# Sheet6.net
KiCad netlist of a schematic drawn in Altium Designer
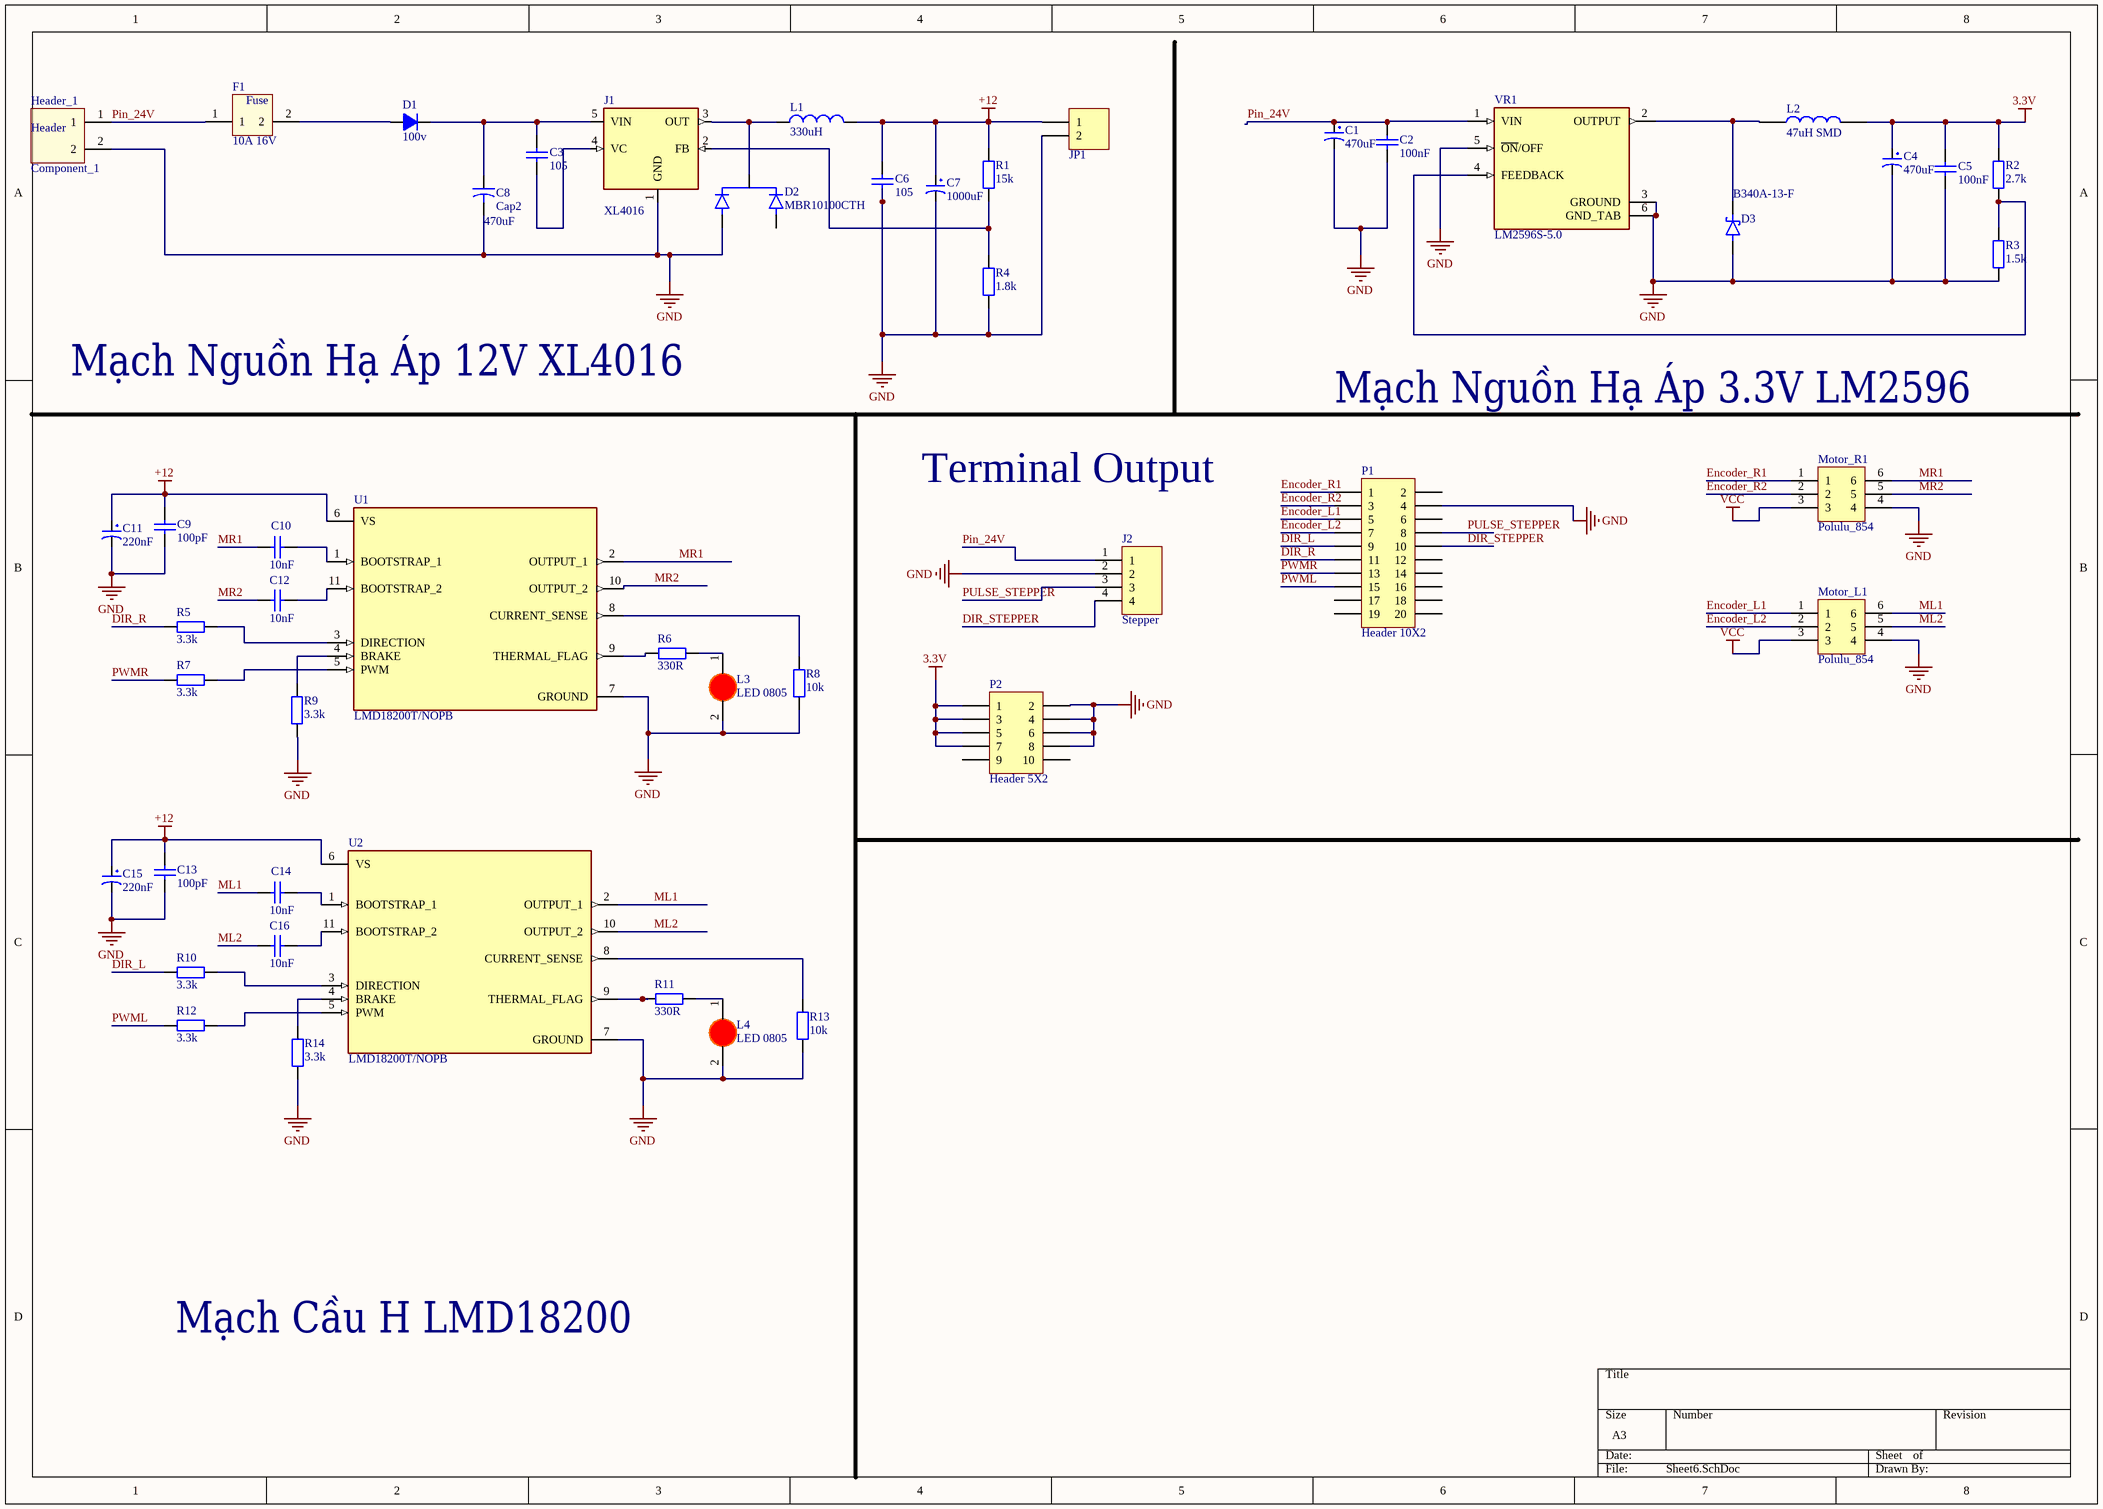
[diagram p0: Sheet6.SchDoc]

(export (version "E")
  (design (tool "Eeschema 10.0.6"))
  (components
    (comp (ref "C1")
      (value "470uF")
      (footprint "tu hoa 8mm")
      (description "Cắm")
      (libsource (lib "Altium_Lib_by_KhueNguyenCreator") (part "Tu Hoa 470uF 16V 8x11"))
    )
    (comp (ref "C2")
      (value "100nF")
      (footprint "tu tantalum dip5.08")
      (description "Cắm")
      (libsource (lib "Altium_Lib_by_KhueNguyenCreator") (part "Tu tantalum 100nF 50V 20% DIP5.08"))
    )
    (comp (ref "C3")
      (value "105")
      (footprint "tu 0805")
      (description "Dán")
      (libsource (lib "Altium_Lib_by_KhueNguyenCreator") (part "Tu 0805 105 50V 10%"))
    )
    (comp (ref "C4")
      (value "470uF")
      (footprint "tu hoa 8mm")
      (description "Cắm")
      (libsource (lib "Altium_Lib_by_KhueNguyenCreator") (part "Tu Hoa 470uF 16V 8x11"))
    )
    (comp (ref "C5")
      (value "100nF")
      (footprint "tu tantalum dip5.08")
      (description "Cắm")
      (libsource (lib "Altium_Lib_by_KhueNguyenCreator") (part "Tu tantalum 100nF 50V 20% DIP5.08"))
    )
    (comp (ref "C6")
      (value "105")
      (footprint "tu 0805")
      (description "Dán")
      (libsource (lib "Altium_Lib_by_KhueNguyenCreator") (part "Tu 0805 105 50V 10%"))
    )
    (comp (ref "C7")
      (value "1000uF")
      (footprint "tu hoa 13mm")
      (description "Cắm")
      (libsource (lib "Altium_Lib_by_KhueNguyenCreator") (part "Tu Hoa 1000uF 50V 13x26"))
    )
    (comp (ref "C8")
      (value "Cap2")
      (footprint "CAPR5-4X5")
      (description "Capacitor")
      (fields (field (name "ALTIUM_VALUE") "470uF") (field (name "PUBLISHER") "Altium Limited"))
      (libsource (lib "Miscellaneous Devices") (part "Cap2"))
    )
    (comp (ref "C9")
      (value "100pF")
      (footprint "tu 1206")
      (description "Dán")
      (libsource (lib "Altium_Lib_by_KhueNguyenCreator") (part "Tu 1206 100pF 50V 5%"))
    )
    (comp (ref "C10")
      (value "10nF")
      (footprint "tu tantalum dip5.08")
      (description "Cắm")
      (libsource (lib "Altium_Lib_by_KhueNguyenCreator") (part "Tu tantalum 10nF DIP5.08"))
    )
    (comp (ref "C11")
      (value "220nF")
      (footprint "tu hoa 8mm")
      (description "Cắm")
      (libsource (lib "Altium_Lib_by_KhueNguyenCreator") (part "Tu Hoa 220uF 35V 8x12"))
    )
    (comp (ref "C12")
      (value "10nF")
      (footprint "tu tantalum dip5.08")
      (description "Cắm")
      (libsource (lib "Altium_Lib_by_KhueNguyenCreator") (part "Tu tantalum 10nF DIP5.08"))
    )
    (comp (ref "C13")
      (value "100pF")
      (footprint "tu 1206")
      (description "Dán")
      (libsource (lib "Altium_Lib_by_KhueNguyenCreator") (part "Tu 1206 100pF 50V 5%"))
    )
    (comp (ref "C14")
      (value "10nF")
      (footprint "tu tantalum dip5.08")
      (description "Cắm")
      (libsource (lib "Altium_Lib_by_KhueNguyenCreator") (part "Tu tantalum 10nF DIP5.08"))
    )
    (comp (ref "C15")
      (value "220nF")
      (footprint "tu hoa 8mm")
      (description "Cắm")
      (libsource (lib "Altium_Lib_by_KhueNguyenCreator") (part "Tu Hoa 220uF 35V 8x12"))
    )
    (comp (ref "C16")
      (value "10nF")
      (footprint "tu tantalum dip5.08")
      (description "Cắm")
      (libsource (lib "Altium_Lib_by_KhueNguyenCreator") (part "Tu tantalum 10nF DIP5.08"))
    )
    (comp (ref "D1")
      (value "100v")
      (footprint "DIODE 1A")
      (description "Cắm")
      (libsource (lib "Altium_Lib_by_KhueNguyenCreator") (part "Diode 1N4007"))
    )
    (comp (ref "D2")
      (value "MBR10100CTH")
      (footprint "TO254P1050X476X2020-3")
      (description "10A, 100V, Schottky Rectifier")
      (fields (field (name "MF") "Taiwan Semiconductor"))
      (libsource (lib "MBR10100CTH") (part "MBR10100CTH"))
    )
    (comp (ref "D3")
      (value "B340A-13-F")
      (footprint "DIOM5226X240N")
      (description "Diode Schottky 40V 3A Surface Mount SMA")
      (fields (field (name "MF") "Diodes Inc."))
      (libsource (lib "Altium_Lib_by_KhueNguyenCreator") (part "B340A-13-F"))
    )
    (comp (ref "F1")
      (value "10A 16V")
      (footprint "Auto_Fuse")
      (libsource (lib "Thu_vien_KA_01") (part "Auto_Fuse_10A"))
    )
    (comp (ref "Header_1")
      (value "Component_1")
      (footprint "CONN-TH_2P-P9.50_HB9500-9.5-2P")
      (libsource (lib "Header_2Pin") (part "Component_1"))
    )
    (comp (ref "J1")
      (value "XL4016")
      (footprint "LM2576T2")
      (fields (field (name "MF") "XLSEMI"))
      (libsource (lib "XL4016") (part "XL4016"))
    )
    (comp (ref "J2")
      (value "Stepper")
      (footprint "CON4_78_B4B-PH-K-S(LF)(SN)")
      (description "Connector Header Through Hole 4 position 0.079\" (2.00mm)")
      (fields
        (field (name "MANUFACTURER PART NUMBER") "B4B-PH-K-S(LF)(SN)")
        (field (name "MANUFACTURER") "JST")
      )
      (libsource (lib "Altium_Lib_by_KhueNguyenCreator") (part "CON-PLG_4X1-78-ST-TH"))
    )
    (comp (ref "JP1")
      (value "Header 2_1")
      (footprint "HED2")
      (description "Header, 2-Pin")
      (fields (field (name "MANUFACTURER") "Generic Components"))
      (libsource (lib "syhaunguyen") (part "Header 2_1"))
    )
    (comp (ref "L1")
      (value "330uH")
      (footprint "IND_30.1MM_TH")
      (description "330uH-10A-CHINESE INDUCTOR")
      (fields (field (name "MANUFACTURER PART NUMBER") "NA"))
      (libsource (lib "Altium_Lib_by_KhueNguyenCreator") (part "IND_330uH-10A-TH"))
    )
    (comp (ref "L2")
      (value "47uH SMD")
      (footprint "Cuon Cam 7x7x5")
      (description "Dán")
      (libsource (lib "Altium_Lib_by_KhueNguyenCreator") (part "CUON CAM 47uH SMD"))
    )
    (comp (ref "L3")
      (value "LED 0805")
      (footprint "LED-0805-Red")
      (description "Dán")
      (libsource (lib "Altium_Lib_by_KhueNguyenCreator") (part "LED 0805 Do"))
    )
    (comp (ref "L4")
      (value "LED 0805")
      (footprint "LED-0805-Red")
      (description "Dán")
      (libsource (lib "Altium_Lib_by_KhueNguyenCreator") (part "LED 0805 Do"))
    )
    (comp (ref "Motor_L1")
      (value "Polulu_854")
      (footprint "CON6_100_59D78_TH_ST - duplicate")
      (fields (field (name "MANUFACTURER") "NA"))
      (libsource (lib "Altium_Lib_by_KhueNguyenCreator") (part "CON-PLG_2X3-100-ST-TH"))
    )
    (comp (ref "Motor_R1")
      (value "Polulu_854")
      (footprint "CON6_100_59D78_TH_ST - duplicate")
      (fields (field (name "MANUFACTURER") "NA"))
      (libsource (lib "Altium_Lib_by_KhueNguyenCreator") (part "CON-PLG_2X3-100-ST-TH"))
    )
    (comp (ref "P1")
      (value "Header 10X2")
      (footprint "HDR2X10")
      (description "Header, 10-Pin, Dual row")
      (fields (field (name "PUBLISHER") "Altium Limited"))
      (libsource (lib "Miscellaneous Connectors") (part "Header 10X2"))
    )
    (comp (ref "P2")
      (value "Header 5X2")
      (footprint "HDR2X5")
      (description "Header, 5-Pin, Dual row")
      (fields (field (name "PUBLISHER") "Altium Limited"))
      (libsource (lib "My library altium") (part "Header 5X2"))
    )
    (comp (ref "R1")
      (value "15k")
      (footprint "tro vach 1/4w")
      (description "Cắm")
      (libsource (lib "Altium_Lib_by_KhueNguyenCreator") (part "Tro Vach 1/4W 5% 15k"))
    )
    (comp (ref "R2")
      (value "2.7k")
      (footprint "tro smd 0805")
      (description "Dán")
      (libsource (lib "Altium_Lib_by_KhueNguyenCreator") (part "Tro 0805 5% 2.7k"))
    )
    (comp (ref "R3")
      (value "1.5k")
      (footprint "tro smd 0805")
      (description "Dán")
      (libsource (lib "Altium_Lib_by_KhueNguyenCreator") (part "Tro 0805 5% 1.5k"))
    )
    (comp (ref "R4")
      (value "1.8k")
      (footprint "tro vach 1/4w")
      (description "Cắm")
      (libsource (lib "Altium_Lib_by_KhueNguyenCreator") (part "Tro Vach 1/4W 5% 1.8k"))
    )
    (comp (ref "R5")
      (value "3.3k")
      (footprint "tro smd 0805")
      (description "Dán")
      (libsource (lib "Altium_Lib_by_KhueNguyenCreator") (part "Tro 0805 5% 3.3k"))
    )
    (comp (ref "R6")
      (value "330R")
      (footprint "Tro SMD 0805")
      (description "Dán")
      (libsource (lib "Altium_Lib_by_KhueNguyenCreator") (part "Tro 0805 5% 330R"))
    )
    (comp (ref "R7")
      (value "3.3k")
      (footprint "tro smd 0805")
      (description "Dán")
      (libsource (lib "Altium_Lib_by_KhueNguyenCreator") (part "Tro 0805 5% 3.3k"))
    )
    (comp (ref "R8")
      (value "10k")
      (footprint "tro smd 0805")
      (description "Dán")
      (libsource (lib "Altium_Lib_by_KhueNguyenCreator") (part "Tro 0805 5% 10k"))
    )
    (comp (ref "R9")
      (value "3.3k")
      (footprint "tro smd 0805")
      (description "Dán")
      (libsource (lib "Altium_Lib_by_KhueNguyenCreator") (part "Tro 0805 5% 3.3k"))
    )
    (comp (ref "R10")
      (value "3.3k")
      (footprint "tro smd 0805")
      (description "Dán")
      (libsource (lib "Altium_Lib_by_KhueNguyenCreator") (part "Tro 0805 5% 3.3k"))
    )
    (comp (ref "R11")
      (value "330R")
      (footprint "Tro SMD 0805")
      (description "Dán")
      (libsource (lib "Altium_Lib_by_KhueNguyenCreator") (part "Tro 0805 5% 330R"))
    )
    (comp (ref "R12")
      (value "3.3k")
      (footprint "tro smd 0805")
      (description "Dán")
      (libsource (lib "Altium_Lib_by_KhueNguyenCreator") (part "Tro 0805 5% 3.3k"))
    )
    (comp (ref "R13")
      (value "10k")
      (footprint "tro smd 0805")
      (description "Dán")
      (libsource (lib "Altium_Lib_by_KhueNguyenCreator") (part "Tro 0805 5% 10k"))
    )
    (comp (ref "R14")
      (value "3.3k")
      (footprint "tro smd 0805")
      (description "Dán")
      (libsource (lib "Altium_Lib_by_KhueNguyenCreator") (part "Tro 0805 5% 3.3k"))
    )
    (comp (ref "U1")
      (value "LMD18200T/NOPB")
      (footprint "LMD18200")
      (libsource (lib "Thu_vien_KA_01") (part "LMD18200T/NOPB"))
    )
    (comp (ref "U2")
      (value "LMD18200T/NOPB")
      (footprint "LMD18200")
      (libsource (lib "Thu_vien_KA_01") (part "LMD18200T/NOPB"))
    )
    (comp (ref "VR1")
      (value "LM2596S-5.0")
      (footprint "TO170P1524X483-6N")
      (description "SIMPLE SWITCHER&reg; 4.5V to 40V, 3A Low Component Count Step-Down Regulator")
      (fields (field (name "MP") "LM2596S-5.0/NOPB") (field (name "MF") "Texas Instruments"))
      (libsource (lib "LM2596S-5.0") (part "LM2596S-5.0"))
    )
  )
  (nets
    (net (code "1") (name "+12") (class "Default")
      (node (ref "C11") (pin "1") (pinfunction "1_1") (pintype "passive"))
      (node (ref "C13") (pin "1") (pinfunction "1_1") (pintype "passive"))
      (node (ref "C15") (pin "1") (pinfunction "1_1") (pintype "passive"))
      (node (ref "C6") (pin "1") (pinfunction "1_1") (pintype "passive"))
      (node (ref "C7") (pin "1") (pinfunction "1_1") (pintype "passive"))
      (node (ref "C9") (pin "1") (pinfunction "1_1") (pintype "passive"))
      (node (ref "JP1") (pin "1") (pinfunction "1_1") (pintype "passive"))
      (node (ref "L1") (pin "2") (pinfunction "2_2") (pintype "passive"))
      (node (ref "R1") (pin "2") (pinfunction "2_2") (pintype "passive"))
      (node (ref "U1") (pin "6") (pinfunction "VS_6") (pintype "power_in"))
      (node (ref "U2") (pin "6") (pinfunction "VS_6") (pintype "power_in"))
    )
    (net (code "2") (name "/DIR_L") (class "Default")
      (node (ref "P1") (pin "9") (pinfunction "9_9") (pintype "passive"))
      (node (ref "R10") (pin "1") (pinfunction "1_1") (pintype "passive"))
    )
    (net (code "3") (name "/DIR_R") (class "Default")
      (node (ref "P1") (pin "11") (pinfunction "11_11") (pintype "passive"))
      (node (ref "R5") (pin "1") (pinfunction "1_1") (pintype "passive"))
    )
    (net (code "4") (name "/DIR_STEPPER") (class "Default")
      (node (ref "J2") (pin "4") (pinfunction "4_4") (pintype "passive"))
      (node (ref "P1") (pin "10") (pinfunction "10_10") (pintype "passive"))
    )
    (net (code "5") (name "/Encoder_L1") (class "Default")
      (node (ref "Motor_L1") (pin "1") (pinfunction "1_1") (pintype "passive"))
      (node (ref "P1") (pin "5") (pinfunction "5_5") (pintype "passive"))
    )
    (net (code "6") (name "/Encoder_L2") (class "Default")
      (node (ref "Motor_L1") (pin "2") (pinfunction "2_2") (pintype "passive"))
      (node (ref "P1") (pin "7") (pinfunction "7_7") (pintype "passive"))
    )
    (net (code "7") (name "/Encoder_R1") (class "Default")
      (node (ref "Motor_R1") (pin "1") (pinfunction "1_1") (pintype "passive"))
      (node (ref "P1") (pin "1") (pinfunction "1_1") (pintype "passive"))
    )
    (net (code "8") (name "/Encoder_R2") (class "Default")
      (node (ref "Motor_R1") (pin "2") (pinfunction "2_2") (pintype "passive"))
      (node (ref "P1") (pin "3") (pinfunction "3_3") (pintype "passive"))
    )
    (net (code "9") (name "/ML1") (class "Default")
      (node (ref "C14") (pin "2") (pinfunction "2_2") (pintype "passive"))
      (node (ref "Motor_L1") (pin "6") (pinfunction "6_6") (pintype "passive"))
      (node (ref "U2") (pin "2") (pinfunction "OUTPUT_1_2") (pintype "output"))
    )
    (net (code "10") (name "/ML2") (class "Default")
      (node (ref "C16") (pin "2") (pinfunction "2_2") (pintype "passive"))
      (node (ref "Motor_L1") (pin "5") (pinfunction "5_5") (pintype "passive"))
      (node (ref "U2") (pin "10") (pinfunction "OUTPUT_2_10") (pintype "output"))
    )
    (net (code "11") (name "/MR1") (class "Default")
      (node (ref "C10") (pin "2") (pinfunction "2_2") (pintype "passive"))
      (node (ref "Motor_R1") (pin "6") (pinfunction "6_6") (pintype "passive"))
      (node (ref "U1") (pin "2") (pinfunction "OUTPUT_1_2") (pintype "output"))
    )
    (net (code "12") (name "/MR2") (class "Default")
      (node (ref "C12") (pin "2") (pinfunction "2_2") (pintype "passive"))
      (node (ref "Motor_R1") (pin "5") (pinfunction "5_5") (pintype "passive"))
      (node (ref "U1") (pin "10") (pinfunction "OUTPUT_2_10") (pintype "output"))
    )
    (net (code "13") (name "/PULSE_STEPPER") (class "Default")
      (node (ref "J2") (pin "3") (pinfunction "3_3") (pintype "passive"))
      (node (ref "P1") (pin "8") (pinfunction "8_8") (pintype "passive"))
    )
    (net (code "14") (name "/PWML") (class "Default")
      (node (ref "P1") (pin "15") (pinfunction "15_15") (pintype "passive"))
      (node (ref "R12") (pin "1") (pinfunction "1_1") (pintype "passive"))
    )
    (net (code "15") (name "/PWMR") (class "Default")
      (node (ref "P1") (pin "13") (pinfunction "13_13") (pintype "passive"))
      (node (ref "R7") (pin "1") (pinfunction "1_1") (pintype "passive"))
    )
    (net (code "16") (name "/Pin_24V") (class "Default")
      (node (ref "C1") (pin "1") (pinfunction "1_1") (pintype "passive"))
      (node (ref "C2") (pin "1") (pinfunction "1_1") (pintype "passive"))
      (node (ref "F1") (pin "1") (pinfunction "1_1") (pintype "passive"))
      (node (ref "Header_1") (pin "1") (pinfunction "1_1") (pintype "passive"))
      (node (ref "J2") (pin "1") (pinfunction "1_1") (pintype "passive"))
      (node (ref "VR1") (pin "1") (pinfunction "VIN_1") (pintype "input"))
    )
    (net (code "17") (name "3.3V") (class "Default")
      (node (ref "C4") (pin "1") (pinfunction "1_1") (pintype "passive"))
      (node (ref "C5") (pin "1") (pinfunction "1_1") (pintype "passive"))
      (node (ref "L2") (pin "2") (pinfunction "2_2") (pintype "passive"))
      (node (ref "P2") (pin "1") (pinfunction "1_1") (pintype "passive"))
      (node (ref "P2") (pin "3") (pinfunction "3_3") (pintype "passive"))
      (node (ref "P2") (pin "5") (pinfunction "5_5") (pintype "passive"))
      (node (ref "P2") (pin "7") (pinfunction "7_7") (pintype "passive"))
      (node (ref "R2") (pin "2") (pinfunction "2_2") (pintype "passive"))
    )
    (net (code "18") (name "GND") (class "Default")
      (node (ref "C1") (pin "2") (pinfunction "2_2") (pintype "passive"))
      (node (ref "C11") (pin "2") (pinfunction "2_2") (pintype "passive"))
      (node (ref "C13") (pin "2") (pinfunction "2_2") (pintype "passive"))
      (node (ref "C15") (pin "2") (pinfunction "2_2") (pintype "passive"))
      (node (ref "C2") (pin "2") (pinfunction "2_2") (pintype "passive"))
      (node (ref "C4") (pin "2") (pinfunction "2_2") (pintype "passive"))
      (node (ref "C5") (pin "2") (pinfunction "2_2") (pintype "passive"))
      (node (ref "C6") (pin "2") (pinfunction "2_2") (pintype "passive"))
      (node (ref "C7") (pin "2") (pinfunction "2_2") (pintype "passive"))
      (node (ref "C8") (pin "2") (pinfunction "2_2") (pintype "passive"))
      (node (ref "C9") (pin "2") (pinfunction "2_2") (pintype "passive"))
      (node (ref "D2") (pin "1") (pinfunction "A1_1") (pintype "passive"))
      (node (ref "D3") (pin "A") (pinfunction "A_A") (pintype "passive"))
      (node (ref "Header_1") (pin "2") (pinfunction "2_2") (pintype "passive"))
      (node (ref "J1") (pin "1") (pinfunction "GND_1") (pintype "power_in"))
      (node (ref "J2") (pin "2") (pinfunction "2_2") (pintype "passive"))
      (node (ref "JP1") (pin "2") (pinfunction "2_2") (pintype "passive"))
      (node (ref "L3") (pin "2") (pinfunction "K_2") (pintype "passive"))
      (node (ref "L4") (pin "2") (pinfunction "K_2") (pintype "passive"))
      (node (ref "Motor_L1") (pin "4") (pinfunction "4_4") (pintype "passive"))
      (node (ref "Motor_R1") (pin "4") (pinfunction "4_4") (pintype "passive"))
      (node (ref "P1") (pin "4") (pinfunction "4_4") (pintype "passive"))
      (node (ref "P2") (pin "2") (pinfunction "2_2") (pintype "passive"))
      (node (ref "P2") (pin "4") (pinfunction "4_4") (pintype "passive"))
      (node (ref "P2") (pin "6") (pinfunction "6_6") (pintype "passive"))
      (node (ref "P2") (pin "8") (pinfunction "8_8") (pintype "passive"))
      (node (ref "R13") (pin "1") (pinfunction "1_1") (pintype "passive"))
      (node (ref "R14") (pin "1") (pinfunction "1_1") (pintype "passive"))
      (node (ref "R3") (pin "1") (pinfunction "1_1") (pintype "passive"))
      (node (ref "R4") (pin "1") (pinfunction "1_1") (pintype "passive"))
      (node (ref "R8") (pin "1") (pinfunction "1_1") (pintype "passive"))
      (node (ref "R9") (pin "1") (pinfunction "1_1") (pintype "passive"))
      (node (ref "U1") (pin "7") (pinfunction "GROUND_7") (pintype "power_in"))
      (node (ref "U2") (pin "7") (pinfunction "GROUND_7") (pintype "power_in"))
      (node (ref "VR1") (pin "3") (pinfunction "GROUND_3") (pintype "power_in"))
      (node (ref "VR1") (pin "5") (pinfunction "~{ON}/OFF_5") (pintype "input"))
      (node (ref "VR1") (pin "6") (pinfunction "GND_TAB_6") (pintype "power_in"))
    )
    (net (code "19") (name "Net-(D1-A)") (class "Default")
      (node (ref "D1") (pin "1") (pinfunction "A_1") (pintype "passive"))
      (node (ref "F1") (pin "2") (pinfunction "2_2") (pintype "passive"))
    )
    (net (code "20") (name "Net-(D1-K)") (class "Default")
      (node (ref "C3") (pin "1") (pinfunction "1_1") (pintype "passive"))
      (node (ref "C8") (pin "1") (pinfunction "1_1") (pintype "passive"))
      (node (ref "D1") (pin "2") (pinfunction "K_2") (pintype "passive"))
      (node (ref "J1") (pin "5") (pinfunction "VIN_5") (pintype "power_in"))
    )
    (net (code "21") (name "Net-(D2-C)") (class "Default")
      (node (ref "D2") (pin "2") (pinfunction "C_2") (pintype "passive"))
      (node (ref "J1") (pin "3") (pinfunction "OUT_3") (pintype "output"))
      (node (ref "L1") (pin "1") (pinfunction "1_1") (pintype "passive"))
    )
    (net (code "22") (name "Net-(J1-FB)") (class "Default")
      (node (ref "J1") (pin "2") (pinfunction "FB_2") (pintype "input"))
      (node (ref "R1") (pin "1") (pinfunction "1_1") (pintype "passive"))
      (node (ref "R4") (pin "2") (pinfunction "2_2") (pintype "passive"))
    )
    (net (code "23") (name "Net-(J1-VC)") (class "Default")
      (node (ref "C3") (pin "2") (pinfunction "2_2") (pintype "passive"))
      (node (ref "J1") (pin "4") (pinfunction "VC_4") (pintype "input"))
    )
    (net (code "24") (name "Net-(L3-A)") (class "Default")
      (node (ref "L3") (pin "1") (pinfunction "A_1") (pintype "passive"))
      (node (ref "R6") (pin "2") (pinfunction "2_2") (pintype "passive"))
    )
    (net (code "25") (name "Net-(L4-A)") (class "Default")
      (node (ref "L4") (pin "1") (pinfunction "A_1") (pintype "passive"))
      (node (ref "R11") (pin "2") (pinfunction "2_2") (pintype "passive"))
    )
    (net (code "26") (name "Net-(U1-BOOTSTRAP_1)") (class "Default")
      (node (ref "C10") (pin "1") (pinfunction "1_1") (pintype "passive"))
      (node (ref "U1") (pin "1") (pinfunction "BOOTSTRAP_1_1") (pintype "input"))
    )
    (net (code "27") (name "Net-(U1-BOOTSTRAP_2)") (class "Default")
      (node (ref "C12") (pin "1") (pinfunction "1_1") (pintype "passive"))
      (node (ref "U1") (pin "11") (pinfunction "BOOTSTRAP_2_11") (pintype "input"))
    )
    (net (code "28") (name "Net-(U1-BRAKE)") (class "Default")
      (node (ref "R9") (pin "2") (pinfunction "2_2") (pintype "passive"))
      (node (ref "U1") (pin "4") (pinfunction "BRAKE_4") (pintype "input"))
    )
    (net (code "29") (name "Net-(U1-CURRENT_SENSE)") (class "Default")
      (node (ref "R8") (pin "2") (pinfunction "2_2") (pintype "passive"))
      (node (ref "U1") (pin "8") (pinfunction "CURRENT_SENSE_8") (pintype "output"))
    )
    (net (code "30") (name "Net-(U1-DIRECTION)") (class "Default")
      (node (ref "R5") (pin "2") (pinfunction "2_2") (pintype "passive"))
      (node (ref "U1") (pin "3") (pinfunction "DIRECTION_3") (pintype "input"))
    )
    (net (code "31") (name "Net-(U1-PWM)") (class "Default")
      (node (ref "R7") (pin "2") (pinfunction "2_2") (pintype "passive"))
      (node (ref "U1") (pin "5") (pinfunction "PWM_5") (pintype "input"))
    )
    (net (code "32") (name "Net-(U1-THERMAL_FLAG)") (class "Default")
      (node (ref "R6") (pin "1") (pinfunction "1_1") (pintype "passive"))
      (node (ref "U1") (pin "9") (pinfunction "THERMAL_FLAG_9") (pintype "output"))
    )
    (net (code "33") (name "Net-(U2-BOOTSTRAP_1)") (class "Default")
      (node (ref "C14") (pin "1") (pinfunction "1_1") (pintype "passive"))
      (node (ref "U2") (pin "1") (pinfunction "BOOTSTRAP_1_1") (pintype "input"))
    )
    (net (code "34") (name "Net-(U2-BOOTSTRAP_2)") (class "Default")
      (node (ref "C16") (pin "1") (pinfunction "1_1") (pintype "passive"))
      (node (ref "U2") (pin "11") (pinfunction "BOOTSTRAP_2_11") (pintype "input"))
    )
    (net (code "35") (name "Net-(U2-BRAKE)") (class "Default")
      (node (ref "R14") (pin "2") (pinfunction "2_2") (pintype "passive"))
      (node (ref "U2") (pin "4") (pinfunction "BRAKE_4") (pintype "input"))
    )
    (net (code "36") (name "Net-(U2-CURRENT_SENSE)") (class "Default")
      (node (ref "R13") (pin "2") (pinfunction "2_2") (pintype "passive"))
      (node (ref "U2") (pin "8") (pinfunction "CURRENT_SENSE_8") (pintype "output"))
    )
    (net (code "37") (name "Net-(U2-DIRECTION)") (class "Default")
      (node (ref "R10") (pin "2") (pinfunction "2_2") (pintype "passive"))
      (node (ref "U2") (pin "3") (pinfunction "DIRECTION_3") (pintype "input"))
    )
    (net (code "38") (name "Net-(U2-PWM)") (class "Default")
      (node (ref "R12") (pin "2") (pinfunction "2_2") (pintype "passive"))
      (node (ref "U2") (pin "5") (pinfunction "PWM_5") (pintype "input"))
    )
    (net (code "39") (name "Net-(U2-THERMAL_FLAG)") (class "Default")
      (node (ref "R11") (pin "1") (pinfunction "1_1") (pintype "passive"))
      (node (ref "U2") (pin "9") (pinfunction "THERMAL_FLAG_9") (pintype "output"))
    )
    (net (code "40") (name "Net-(VR1-FEEDBACK)") (class "Default")
      (node (ref "R2") (pin "1") (pinfunction "1_1") (pintype "passive"))
      (node (ref "R3") (pin "2") (pinfunction "2_2") (pintype "passive"))
      (node (ref "VR1") (pin "4") (pinfunction "FEEDBACK_4") (pintype "input"))
    )
    (net (code "41") (name "Net-(VR1-OUTPUT)") (class "Default")
      (node (ref "D3") (pin "C") (pinfunction "C_C") (pintype "passive"))
      (node (ref "L2") (pin "1") (pinfunction "1_1") (pintype "passive"))
      (node (ref "VR1") (pin "2") (pinfunction "OUTPUT_2") (pintype "output"))
    )
    (net (code "42") (name "VCC") (class "Default")
      (node (ref "Motor_L1") (pin "3") (pinfunction "3_3") (pintype "passive"))
      (node (ref "Motor_R1") (pin "3") (pinfunction "3_3") (pintype "passive"))
    )
    (net (code "43") (name "unconnected-(D2-A2-Pad3)") (class "Default")
      (node (ref "D2") (pin "3") (pinfunction "A2_3") (pintype "passive"))
    )
    (net (code "44") (name "unconnected-(P1-Pad2)") (class "Default")
      (node (ref "P1") (pin "2") (pinfunction "2_2") (pintype "passive"))
    )
    (net (code "45") (name "unconnected-(P1-Pad6)") (class "Default")
      (node (ref "P1") (pin "6") (pinfunction "6_6") (pintype "passive"))
    )
    (net (code "46") (name "unconnected-(P1-Pad12)") (class "Default")
      (node (ref "P1") (pin "12") (pinfunction "12_12") (pintype "passive"))
    )
    (net (code "47") (name "unconnected-(P1-Pad14)") (class "Default")
      (node (ref "P1") (pin "14") (pinfunction "14_14") (pintype "passive"))
    )
    (net (code "48") (name "unconnected-(P1-Pad16)") (class "Default")
      (node (ref "P1") (pin "16") (pinfunction "16_16") (pintype "passive"))
    )
    (net (code "49") (name "unconnected-(P1-Pad17)") (class "Default")
      (node (ref "P1") (pin "17") (pinfunction "17_17") (pintype "passive"))
    )
    (net (code "50") (name "unconnected-(P1-Pad18)") (class "Default")
      (node (ref "P1") (pin "18") (pinfunction "18_18") (pintype "passive"))
    )
    (net (code "51") (name "unconnected-(P1-Pad19)") (class "Default")
      (node (ref "P1") (pin "19") (pinfunction "19_19") (pintype "passive"))
    )
    (net (code "52") (name "unconnected-(P1-Pad20)") (class "Default")
      (node (ref "P1") (pin "20") (pinfunction "20_20") (pintype "passive"))
    )
    (net (code "53") (name "unconnected-(P2-Pad9)") (class "Default")
      (node (ref "P2") (pin "9") (pinfunction "9_9") (pintype "passive"))
    )
    (net (code "54") (name "unconnected-(P2-Pad10)") (class "Default")
      (node (ref "P2") (pin "10") (pinfunction "10_10") (pintype "passive"))
    )
  )
)
